# Do.net
KiCad netlist of a schematic drawn in Altium Designer
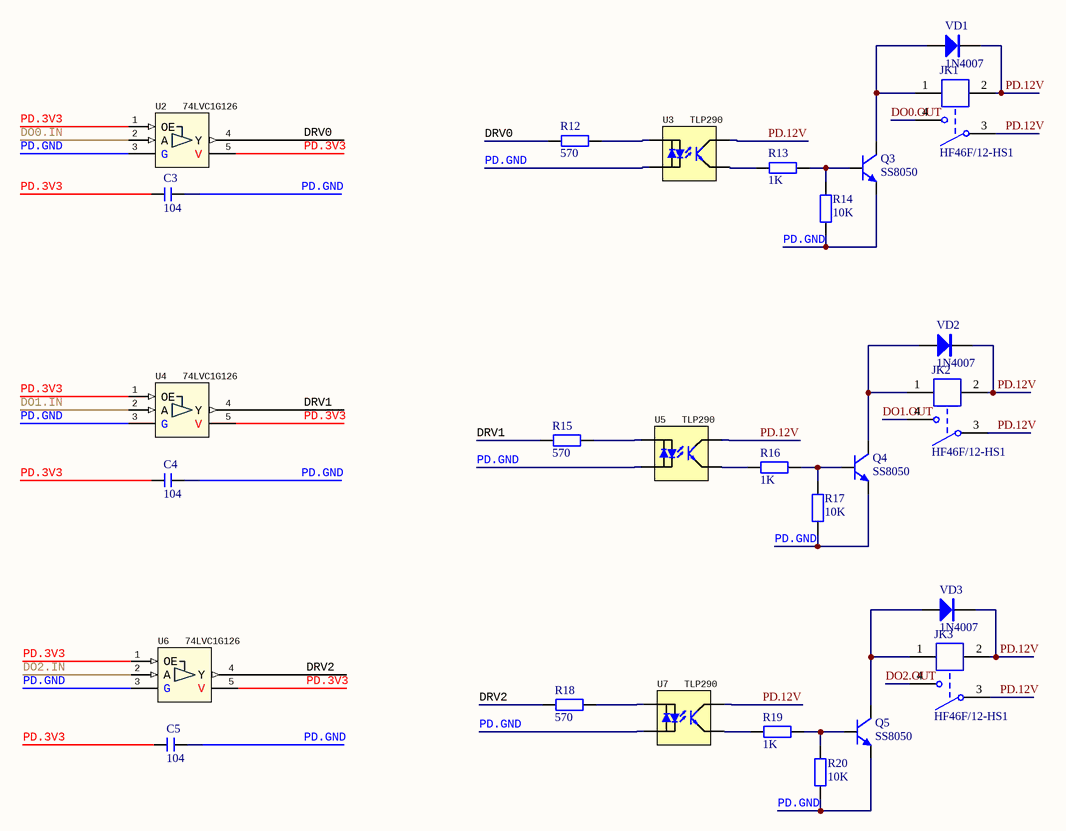
[diagram p0: Do.SchDoc]

(export (version "E")
  (design (tool "Eeschema 10.0.6"))
  (components
    (comp (ref "C3")
      (value "104")
      (footprint "C 0603")
      (description "无极性贴片电容")
      (fields (field (name "版权归属") "源创客"))
      (libsource (lib "电阻-电容-电感") (part "C"))
    )
    (comp (ref "C4")
      (value "104")
      (footprint "C 0603")
      (description "无极性贴片电容")
      (fields (field (name "版权归属") "源创客"))
      (libsource (lib "电阻-电容-电感") (part "C"))
    )
    (comp (ref "C5")
      (value "104")
      (footprint "C 0603")
      (description "无极性贴片电容")
      (fields (field (name "版权归属") "源创客"))
      (libsource (lib "电阻-电容-电感") (part "C"))
    )
    (comp (ref "JK1")
      (value "HF46F/12-HS1")
      (footprint "HF46F/12-HS1")
      (description "12V一组常开")
      (fields (field (name "版权归属") "源创客"))
      (libsource (lib "7.1   - 继电器") (part "HF46F/12-HS1"))
    )
    (comp (ref "JK2")
      (value "HF46F/12-HS1")
      (footprint "HF46F/12-HS1")
      (description "12V一组常开")
      (fields (field (name "版权归属") "源创客"))
      (libsource (lib "7.1   - 继电器") (part "HF46F/12-HS1"))
    )
    (comp (ref "JK3")
      (value "HF46F/12-HS1")
      (footprint "HF46F/12-HS1")
      (description "12V一组常开")
      (fields (field (name "版权归属") "源创客"))
      (libsource (lib "7.1   - 继电器") (part "HF46F/12-HS1"))
    )
    (comp (ref "Q3")
      (value "SS8050")
      (footprint "SOT23-3N")
      (description "高频放大-NPN型")
      (fields (field (name "版权归属") "源创客"))
      (libsource (lib "三极管") (part "8050-SMD"))
    )
    (comp (ref "Q4")
      (value "SS8050")
      (footprint "SOT23-3N")
      (description "高频放大-NPN型")
      (fields (field (name "版权归属") "源创客"))
      (libsource (lib "三极管") (part "8050-SMD"))
    )
    (comp (ref "Q5")
      (value "SS8050")
      (footprint "SOT23-3N")
      (description "高频放大-NPN型")
      (fields (field (name "版权归属") "源创客"))
      (libsource (lib "三极管") (part "8050-SMD"))
    )
    (comp (ref "R12")
      (value "570")
      (footprint "R 0603")
      (description "贴片电阻")
      (fields (field (name "版权归属") "源创客"))
      (libsource (lib "电阻-电容-电感") (part "R"))
    )
    (comp (ref "R13")
      (value "1K")
      (footprint "R 0603")
      (description "贴片电阻")
      (fields (field (name "版权归属") "源创客"))
      (libsource (lib "电阻-电容-电感") (part "R"))
    )
    (comp (ref "R14")
      (value "10K")
      (footprint "R 0603")
      (description "贴片电阻")
      (fields (field (name "版权归属") "源创客"))
      (libsource (lib "电阻-电容-电感") (part "R"))
    )
    (comp (ref "R15")
      (value "570")
      (footprint "R 0603")
      (description "贴片电阻")
      (fields (field (name "版权归属") "源创客"))
      (libsource (lib "电阻-电容-电感") (part "R"))
    )
    (comp (ref "R16")
      (value "1K")
      (footprint "R 0603")
      (description "贴片电阻")
      (fields (field (name "版权归属") "源创客"))
      (libsource (lib "电阻-电容-电感") (part "R"))
    )
    (comp (ref "R17")
      (value "10K")
      (footprint "R 0603")
      (description "贴片电阻")
      (fields (field (name "版权归属") "源创客"))
      (libsource (lib "电阻-电容-电感") (part "R"))
    )
    (comp (ref "R18")
      (value "570")
      (footprint "R 0603")
      (description "贴片电阻")
      (fields (field (name "版权归属") "源创客"))
      (libsource (lib "电阻-电容-电感") (part "R"))
    )
    (comp (ref "R19")
      (value "1K")
      (footprint "R 0603")
      (description "贴片电阻")
      (fields (field (name "版权归属") "源创客"))
      (libsource (lib "电阻-电容-电感") (part "R"))
    )
    (comp (ref "R20")
      (value "10K")
      (footprint "R 0603")
      (description "贴片电阻")
      (fields (field (name "版权归属") "源创客"))
      (libsource (lib "电阻-电容-电感") (part "R"))
    )
    (comp (ref "U2")
      (value "74LVC1G126")
      (footprint "TSSOP-5P-0.65BSC-2.15x1.40Bmax-1.10Hmax")
      (description "U-LVC1G126")
      (libsource (lib "TKAI0163WP01-01") (part "74LVC1G126"))
    )
    (comp (ref "U3")
      (value "TLP290")
      (footprint "SO-4-1.27BSC-4.6W-TLP")
      (description "U-TLP290")
      (libsource (lib "TKAI0163WP01-01") (part "TLP290"))
    )
    (comp (ref "U4")
      (value "74LVC1G126")
      (footprint "TSSOP-5P-0.65BSC-2.15x1.40Bmax-1.10Hmax")
      (description "U-LVC1G126")
      (libsource (lib "TKAI0163WP01-01") (part "74LVC1G126"))
    )
    (comp (ref "U5")
      (value "TLP290")
      (footprint "SO-4-1.27BSC-4.6W-TLP")
      (description "U-TLP290")
      (libsource (lib "TKAI0163WP01-01") (part "TLP290"))
    )
    (comp (ref "U6")
      (value "74LVC1G126")
      (footprint "TSSOP-5P-0.65BSC-2.15x1.40Bmax-1.10Hmax")
      (description "U-LVC1G126")
      (libsource (lib "TKAI0163WP01-01") (part "74LVC1G126"))
    )
    (comp (ref "U7")
      (value "TLP290")
      (footprint "SO-4-1.27BSC-4.6W-TLP")
      (description "U-TLP290")
      (libsource (lib "TKAI0163WP01-01") (part "TLP290"))
    )
    (comp (ref "VD1")
      (value "1N4007")
      (footprint "SMA")
      (description "整流二极管")
      (fields (field (name "版权归属") "源创客"))
      (libsource (lib "二极管-整流桥") (part "1N4007"))
    )
    (comp (ref "VD2")
      (value "1N4007")
      (footprint "SMA")
      (description "整流二极管")
      (fields (field (name "版权归属") "源创客"))
      (libsource (lib "二极管-整流桥") (part "1N4007"))
    )
    (comp (ref "VD3")
      (value "1N4007")
      (footprint "SMA")
      (description "整流二极管")
      (fields (field (name "版权归属") "源创客"))
      (libsource (lib "二极管-整流桥") (part "1N4007"))
    )
  )
  (nets
    (net (code "1") (name "/DO0.IN") (class "Default")
      (node (ref "U2") (pin "2") (pinfunction "A_2") (pintype "input"))
    )
    (net (code "2") (name "/DO0.OUT") (class "Default")
      (node (ref "JK1") (pin "4") (pinfunction "4_4") (pintype "passive"))
    )
    (net (code "3") (name "/DO1.IN") (class "Default")
      (node (ref "U4") (pin "2") (pinfunction "A_2") (pintype "input"))
    )
    (net (code "4") (name "/DO1.OUT") (class "Default")
      (node (ref "JK2") (pin "4") (pinfunction "4_4") (pintype "passive"))
    )
    (net (code "5") (name "/DO2.IN") (class "Default")
      (node (ref "U6") (pin "2") (pinfunction "A_2") (pintype "input"))
    )
    (net (code "6") (name "/DO2.OUT") (class "Default")
      (node (ref "JK3") (pin "4") (pinfunction "4_4") (pintype "passive"))
    )
    (net (code "7") (name "/DRV0") (class "Default")
      (node (ref "R12") (pin "1") (pinfunction "1_1") (pintype "passive"))
      (node (ref "U2") (pin "4") (pinfunction "Y_4") (pintype "output"))
    )
    (net (code "8") (name "/DRV1") (class "Default")
      (node (ref "R15") (pin "1") (pinfunction "1_1") (pintype "passive"))
      (node (ref "U4") (pin "4") (pinfunction "Y_4") (pintype "output"))
    )
    (net (code "9") (name "/DRV2") (class "Default")
      (node (ref "R18") (pin "1") (pinfunction "1_1") (pintype "passive"))
      (node (ref "U6") (pin "4") (pinfunction "Y_4") (pintype "output"))
    )
    (net (code "10") (name "/PD.3V3") (class "Default")
      (node (ref "C3") (pin "2") (pinfunction "2_2") (pintype "passive"))
      (node (ref "C4") (pin "2") (pinfunction "2_2") (pintype "passive"))
      (node (ref "C5") (pin "2") (pinfunction "2_2") (pintype "passive"))
      (node (ref "U2") (pin "1") (pinfunction "OE_1") (pintype "input"))
      (node (ref "U2") (pin "5") (pinfunction "V_5") (pintype "power_in"))
      (node (ref "U4") (pin "1") (pinfunction "OE_1") (pintype "input"))
      (node (ref "U4") (pin "5") (pinfunction "V_5") (pintype "power_in"))
      (node (ref "U6") (pin "1") (pinfunction "OE_1") (pintype "input"))
      (node (ref "U6") (pin "5") (pinfunction "V_5") (pintype "power_in"))
    )
    (net (code "11") (name "/PD.12V") (class "Default")
      (node (ref "JK1") (pin "2") (pinfunction "2_2") (pintype "passive"))
      (node (ref "JK1") (pin "3") (pinfunction "3_3") (pintype "passive"))
      (node (ref "JK2") (pin "2") (pinfunction "2_2") (pintype "passive"))
      (node (ref "JK2") (pin "3") (pinfunction "3_3") (pintype "passive"))
      (node (ref "JK3") (pin "2") (pinfunction "2_2") (pintype "passive"))
      (node (ref "JK3") (pin "3") (pinfunction "3_3") (pintype "passive"))
      (node (ref "U3") (pin "4") (pinfunction "4_4") (pintype "passive"))
      (node (ref "U5") (pin "4") (pinfunction "4_4") (pintype "passive"))
      (node (ref "U7") (pin "4") (pinfunction "4_4") (pintype "passive"))
      (node (ref "VD1") (pin "2") (pinfunction "K_2") (pintype "passive"))
      (node (ref "VD2") (pin "2") (pinfunction "K_2") (pintype "passive"))
      (node (ref "VD3") (pin "2") (pinfunction "K_2") (pintype "passive"))
    )
    (net (code "12") (name "/PD.GND") (class "Default")
      (node (ref "C3") (pin "1") (pinfunction "1_1") (pintype "passive"))
      (node (ref "C4") (pin "1") (pinfunction "1_1") (pintype "passive"))
      (node (ref "C5") (pin "1") (pinfunction "1_1") (pintype "passive"))
      (node (ref "Q3") (pin "2") (pinfunction "E_2") (pintype "passive"))
      (node (ref "Q4") (pin "2") (pinfunction "E_2") (pintype "passive"))
      (node (ref "Q5") (pin "2") (pinfunction "E_2") (pintype "passive"))
      (node (ref "R14") (pin "1") (pinfunction "1_1") (pintype "passive"))
      (node (ref "R17") (pin "1") (pinfunction "1_1") (pintype "passive"))
      (node (ref "R20") (pin "1") (pinfunction "1_1") (pintype "passive"))
      (node (ref "U2") (pin "3") (pinfunction "G_3") (pintype "power_in"))
      (node (ref "U3") (pin "2") (pinfunction "2_2") (pintype "passive"))
      (node (ref "U4") (pin "3") (pinfunction "G_3") (pintype "power_in"))
      (node (ref "U5") (pin "2") (pinfunction "2_2") (pintype "passive"))
      (node (ref "U6") (pin "3") (pinfunction "G_3") (pintype "power_in"))
      (node (ref "U7") (pin "2") (pinfunction "2_2") (pintype "passive"))
    )
    (net (code "13") (name "Net-(Q3-B)") (class "Default")
      (node (ref "Q3") (pin "1") (pinfunction "B_1") (pintype "passive"))
      (node (ref "R13") (pin "2") (pinfunction "2_2") (pintype "passive"))
      (node (ref "R14") (pin "2") (pinfunction "2_2") (pintype "passive"))
    )
    (net (code "14") (name "Net-(Q3-C)") (class "Default")
      (node (ref "JK1") (pin "1") (pinfunction "1_1") (pintype "passive"))
      (node (ref "Q3") (pin "3") (pinfunction "C_3") (pintype "passive"))
      (node (ref "VD1") (pin "1") (pinfunction "A_1") (pintype "passive"))
    )
    (net (code "15") (name "Net-(Q4-B)") (class "Default")
      (node (ref "Q4") (pin "1") (pinfunction "B_1") (pintype "passive"))
      (node (ref "R16") (pin "2") (pinfunction "2_2") (pintype "passive"))
      (node (ref "R17") (pin "2") (pinfunction "2_2") (pintype "passive"))
    )
    (net (code "16") (name "Net-(Q4-C)") (class "Default")
      (node (ref "JK2") (pin "1") (pinfunction "1_1") (pintype "passive"))
      (node (ref "Q4") (pin "3") (pinfunction "C_3") (pintype "passive"))
      (node (ref "VD2") (pin "1") (pinfunction "A_1") (pintype "passive"))
    )
    (net (code "17") (name "Net-(Q5-B)") (class "Default")
      (node (ref "Q5") (pin "1") (pinfunction "B_1") (pintype "passive"))
      (node (ref "R19") (pin "2") (pinfunction "2_2") (pintype "passive"))
      (node (ref "R20") (pin "2") (pinfunction "2_2") (pintype "passive"))
    )
    (net (code "18") (name "Net-(Q5-C)") (class "Default")
      (node (ref "JK3") (pin "1") (pinfunction "1_1") (pintype "passive"))
      (node (ref "Q5") (pin "3") (pinfunction "C_3") (pintype "passive"))
      (node (ref "VD3") (pin "1") (pinfunction "A_1") (pintype "passive"))
    )
    (net (code "19") (name "Net-(R12-Pad2)") (class "Default")
      (node (ref "R12") (pin "2") (pinfunction "2_2") (pintype "passive"))
      (node (ref "U3") (pin "1") (pinfunction "1_1") (pintype "passive"))
    )
    (net (code "20") (name "Net-(R13-Pad1)") (class "Default")
      (node (ref "R13") (pin "1") (pinfunction "1_1") (pintype "passive"))
      (node (ref "U3") (pin "3") (pinfunction "3_3") (pintype "passive"))
    )
    (net (code "21") (name "Net-(R15-Pad2)") (class "Default")
      (node (ref "R15") (pin "2") (pinfunction "2_2") (pintype "passive"))
      (node (ref "U5") (pin "1") (pinfunction "1_1") (pintype "passive"))
    )
    (net (code "22") (name "Net-(R16-Pad1)") (class "Default")
      (node (ref "R16") (pin "1") (pinfunction "1_1") (pintype "passive"))
      (node (ref "U5") (pin "3") (pinfunction "3_3") (pintype "passive"))
    )
    (net (code "23") (name "Net-(R18-Pad2)") (class "Default")
      (node (ref "R18") (pin "2") (pinfunction "2_2") (pintype "passive"))
      (node (ref "U7") (pin "1") (pinfunction "1_1") (pintype "passive"))
    )
    (net (code "24") (name "Net-(R19-Pad1)") (class "Default")
      (node (ref "R19") (pin "1") (pinfunction "1_1") (pintype "passive"))
      (node (ref "U7") (pin "3") (pinfunction "3_3") (pintype "passive"))
    )
  )
)
